# RS485-board.net
KiCad netlist of a schematic drawn in EAGLE
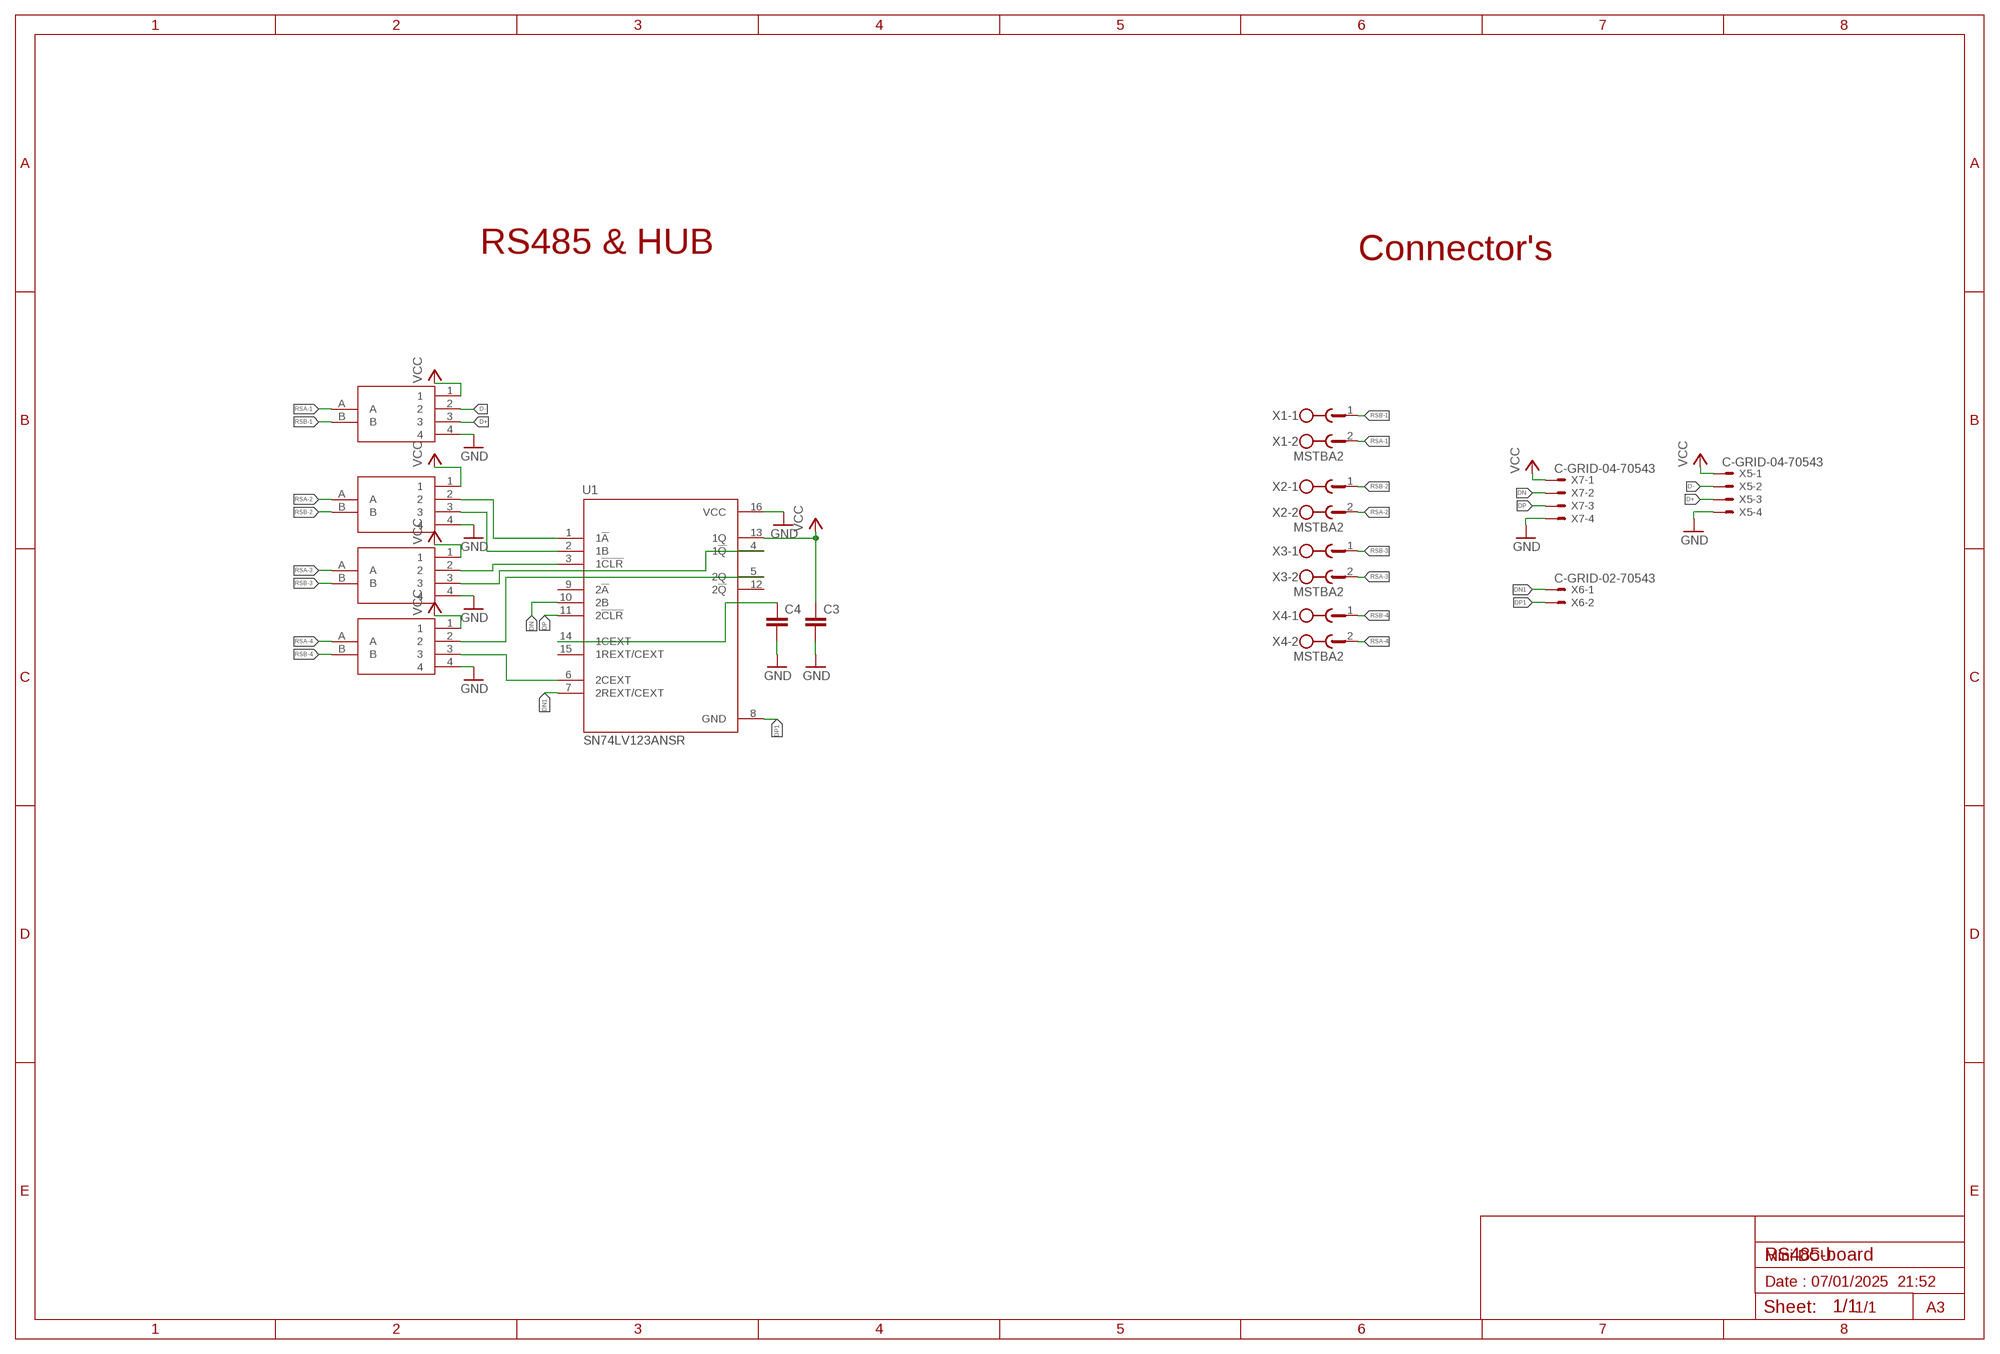
[diagram p0: schematic, sheet 1]

(export (version "E")
  (design (tool "Eeschema 10.0.6"))
  (components
    (comp (ref "C3")
      (value "C-EUC0603K")
      (footprint "eagle-import:C0603K")
      (libsource (lib "eagle-import") (part "C-EUC0603K"))
    )
    (comp (ref "C4")
      (value "C-EUC0603K")
      (footprint "eagle-import:C0603K")
      (libsource (lib "eagle-import") (part "C-EUC0603K"))
    )
    (comp (ref "U1")
      (value "SN74LV123ANSR")
      (footprint "eagle-import:SOIC127P780X200-16N")
      (fields (field (name "DIGIKEY_PART_NUMBER") "296-46201-2-ND") (field (name "MF") "Texas Instruments"))
      (libsource (lib "eagle-import") (part "SN74LV123ANSR"))
    )
    (comp (ref "USB2RS1")
      (value "USB2RS485")
      (footprint "eagle-import:USB2RS485")
      (libsource (lib "eagle-import") (part "USB2RS485"))
    )
    (comp (ref "USB2RS2")
      (value "USB2RS485")
      (footprint "eagle-import:USB2RS485")
      (libsource (lib "eagle-import") (part "USB2RS485"))
    )
    (comp (ref "USB2RS3")
      (value "USB2RS485")
      (footprint "eagle-import:USB2RS485")
      (libsource (lib "eagle-import") (part "USB2RS485"))
    )
    (comp (ref "USB2RS5")
      (value "USB2RS485")
      (footprint "eagle-import:USB2RS485")
      (libsource (lib "eagle-import") (part "USB2RS485"))
    )
    (comp (ref "X1")
      (value "MSTBA2")
      (footprint "eagle-import:MSTBA2")
      (fields (field (name "MF") "FARNELL") (field (name "MPN") "1757242"))
      (libsource (lib "eagle-import") (part "MSTBA2"))
    )
    (comp (ref "X2")
      (value "MSTBA2")
      (footprint "eagle-import:MSTBA2")
      (fields (field (name "MF") "FARNELL") (field (name "MPN") "1757242"))
      (libsource (lib "eagle-import") (part "MSTBA2"))
    )
    (comp (ref "X3")
      (value "MSTBA2")
      (footprint "eagle-import:MSTBA2")
      (fields (field (name "MF") "FARNELL") (field (name "MPN") "1757242"))
      (libsource (lib "eagle-import") (part "MSTBA2"))
    )
    (comp (ref "X4")
      (value "MSTBA2")
      (footprint "eagle-import:MSTBA2")
      (fields (field (name "MF") "FARNELL") (field (name "MPN") "1757242"))
      (libsource (lib "eagle-import") (part "MSTBA2"))
    )
    (comp (ref "X5")
      (value "C-GRID-04-70543")
      (footprint "eagle-import:70543-04")
      (fields (field (name "MF") "MOLEX"))
      (libsource (lib "eagle-import") (part "C-GRID-04-70543"))
    )
    (comp (ref "X6")
      (value "C-GRID-02-70543")
      (footprint "eagle-import:70543-02")
      (fields (field (name "MF") "MOLEX"))
      (libsource (lib "eagle-import") (part "C-GRID-02-70543"))
    )
    (comp (ref "X7")
      (value "C-GRID-04-70543")
      (footprint "eagle-import:70543-04")
      (fields (field (name "MF") "MOLEX"))
      (libsource (lib "eagle-import") (part "C-GRID-04-70543"))
    )
  )
  (nets
    (net (code "1") (name "D+") (class "Default")
      (node (ref "USB2RS5") (pin "3") (pinfunction "3_3") (pintype "bidirectional"))
      (node (ref "X5") (pin "3") (pinfunction "S_3") (pintype "passive"))
    )
    (net (code "2") (name "D-") (class "Default")
      (node (ref "USB2RS5") (pin "2") (pinfunction "2_2") (pintype "bidirectional"))
      (node (ref "X5") (pin "2") (pinfunction "S_2") (pintype "passive"))
    )
    (net (code "3") (name "DN") (class "Default")
      (node (ref "U1") (pin "10") (pinfunction "2B_10") (pintype "input"))
      (node (ref "X7") (pin "2") (pinfunction "S_2") (pintype "passive"))
    )
    (net (code "4") (name "DN1") (class "Default")
      (node (ref "U1") (pin "7") (pinfunction "2REXT/CEXT_7") (pintype "bidirectional"))
      (node (ref "X6") (pin "1") (pinfunction "S_1") (pintype "passive"))
    )
    (net (code "5") (name "DP") (class "Default")
      (node (ref "U1") (pin "11") (pinfunction "2~{CLR}_11") (pintype "input"))
      (node (ref "X7") (pin "3") (pinfunction "S_3") (pintype "passive"))
    )
    (net (code "6") (name "DP1") (class "Default")
      (node (ref "U1") (pin "8") (pinfunction "GND_8") (pintype "power_in"))
      (node (ref "X6") (pin "2") (pinfunction "S_2") (pintype "passive"))
    )
    (net (code "7") (name "GND") (class "Default")
      (node (ref "C3") (pin "2") (pinfunction "2_2") (pintype "passive"))
      (node (ref "C4") (pin "2") (pinfunction "2_2") (pintype "passive"))
      (node (ref "U1") (pin "16") (pinfunction "VCC_16") (pintype "power_in"))
      (node (ref "USB2RS1") (pin "4") (pinfunction "4_4") (pintype "bidirectional"))
      (node (ref "USB2RS2") (pin "4") (pinfunction "4_4") (pintype "bidirectional"))
      (node (ref "USB2RS3") (pin "4") (pinfunction "4_4") (pintype "bidirectional"))
      (node (ref "USB2RS5") (pin "4") (pinfunction "4_4") (pintype "bidirectional"))
      (node (ref "X5") (pin "4") (pinfunction "S_4") (pintype "passive"))
      (node (ref "X7") (pin "4") (pinfunction "S_4") (pintype "passive"))
    )
    (net (code "8") (name "Net-(U1-1B)") (class "Default")
      (node (ref "U1") (pin "2") (pinfunction "1B_2") (pintype "input"))
      (node (ref "USB2RS1") (pin "3") (pinfunction "3_3") (pintype "bidirectional"))
    )
    (net (code "9") (name "Net-(U1-1CEXT)") (class "Default")
      (node (ref "C4") (pin "1") (pinfunction "1_1") (pintype "passive"))
      (node (ref "U1") (pin "14") (pinfunction "1CEXT_14") (pintype "bidirectional"))
    )
    (net (code "10") (name "Net-(U1-1~{A})") (class "Default")
      (node (ref "U1") (pin "1") (pinfunction "1~{A}_1") (pintype "input"))
      (node (ref "USB2RS1") (pin "2") (pinfunction "2_2") (pintype "bidirectional"))
    )
    (net (code "11") (name "Net-(U1-1~{CLR})") (class "Default")
      (node (ref "U1") (pin "3") (pinfunction "1~{CLR}_3") (pintype "input"))
      (node (ref "USB2RS2") (pin "2") (pinfunction "2_2") (pintype "bidirectional"))
    )
    (net (code "12") (name "Net-(U1-1~{Q})") (class "Default")
      (node (ref "U1") (pin "4") (pinfunction "1~{Q}_4") (pintype "output"))
      (node (ref "USB2RS2") (pin "3") (pinfunction "3_3") (pintype "bidirectional"))
    )
    (net (code "13") (name "Net-(U1-2CEXT)") (class "Default")
      (node (ref "U1") (pin "6") (pinfunction "2CEXT_6") (pintype "bidirectional"))
      (node (ref "USB2RS3") (pin "3") (pinfunction "3_3") (pintype "bidirectional"))
    )
    (net (code "14") (name "Net-(U1-2Q)") (class "Default")
      (node (ref "U1") (pin "5") (pinfunction "2Q_5") (pintype "output"))
      (node (ref "USB2RS3") (pin "2") (pinfunction "2_2") (pintype "bidirectional"))
    )
    (net (code "15") (name "RSA-1") (class "Default")
      (node (ref "USB2RS5") (pin "A") (pinfunction "A_A") (pintype "bidirectional"))
      (node (ref "X1") (pin "2") (pinfunction "1_2") (pintype "passive"))
    )
    (net (code "16") (name "RSA-2") (class "Default")
      (node (ref "USB2RS1") (pin "A") (pinfunction "A_A") (pintype "bidirectional"))
      (node (ref "X2") (pin "2") (pinfunction "1_2") (pintype "passive"))
    )
    (net (code "17") (name "RSA-3") (class "Default")
      (node (ref "USB2RS2") (pin "A") (pinfunction "A_A") (pintype "bidirectional"))
      (node (ref "X3") (pin "2") (pinfunction "1_2") (pintype "passive"))
    )
    (net (code "18") (name "RSA-4") (class "Default")
      (node (ref "USB2RS3") (pin "A") (pinfunction "A_A") (pintype "bidirectional"))
      (node (ref "X4") (pin "2") (pinfunction "1_2") (pintype "passive"))
    )
    (net (code "19") (name "RSB-1") (class "Default")
      (node (ref "USB2RS5") (pin "B") (pinfunction "B_B") (pintype "bidirectional"))
      (node (ref "X1") (pin "1") (pinfunction "1_1") (pintype "passive"))
    )
    (net (code "20") (name "RSB-2") (class "Default")
      (node (ref "USB2RS1") (pin "B") (pinfunction "B_B") (pintype "bidirectional"))
      (node (ref "X2") (pin "1") (pinfunction "1_1") (pintype "passive"))
    )
    (net (code "21") (name "RSB-3") (class "Default")
      (node (ref "USB2RS2") (pin "B") (pinfunction "B_B") (pintype "bidirectional"))
      (node (ref "X3") (pin "1") (pinfunction "1_1") (pintype "passive"))
    )
    (net (code "22") (name "RSB-4") (class "Default")
      (node (ref "USB2RS3") (pin "B") (pinfunction "B_B") (pintype "bidirectional"))
      (node (ref "X4") (pin "1") (pinfunction "1_1") (pintype "passive"))
    )
    (net (code "23") (name "VCC") (class "Default")
      (node (ref "C3") (pin "1") (pinfunction "1_1") (pintype "passive"))
      (node (ref "U1") (pin "13") (pinfunction "1Q_13") (pintype "output"))
      (node (ref "USB2RS1") (pin "1") (pinfunction "1_1") (pintype "bidirectional"))
      (node (ref "USB2RS2") (pin "1") (pinfunction "1_1") (pintype "bidirectional"))
      (node (ref "USB2RS3") (pin "1") (pinfunction "1_1") (pintype "bidirectional"))
      (node (ref "USB2RS5") (pin "1") (pinfunction "1_1") (pintype "bidirectional"))
      (node (ref "X5") (pin "1") (pinfunction "S_1") (pintype "passive"))
      (node (ref "X7") (pin "1") (pinfunction "S_1") (pintype "passive"))
    )
    (net (code "24") (name "unconnected-(U1-1REXT{slash}CEXT-Pad15)") (class "Default")
      (node (ref "U1") (pin "15") (pinfunction "1REXT/CEXT_15") (pintype "bidirectional"))
    )
    (net (code "25") (name "unconnected-(U1-2~{A}-Pad9)") (class "Default")
      (node (ref "U1") (pin "9") (pinfunction "2~{A}_9") (pintype "input"))
    )
    (net (code "26") (name "unconnected-(U1-2~{Q}-Pad12)") (class "Default")
      (node (ref "U1") (pin "12") (pinfunction "2~{Q}_12") (pintype "output"))
    )
  )
)
